# Backplane.net
KiCad netlist of a schematic drawn in EAGLE
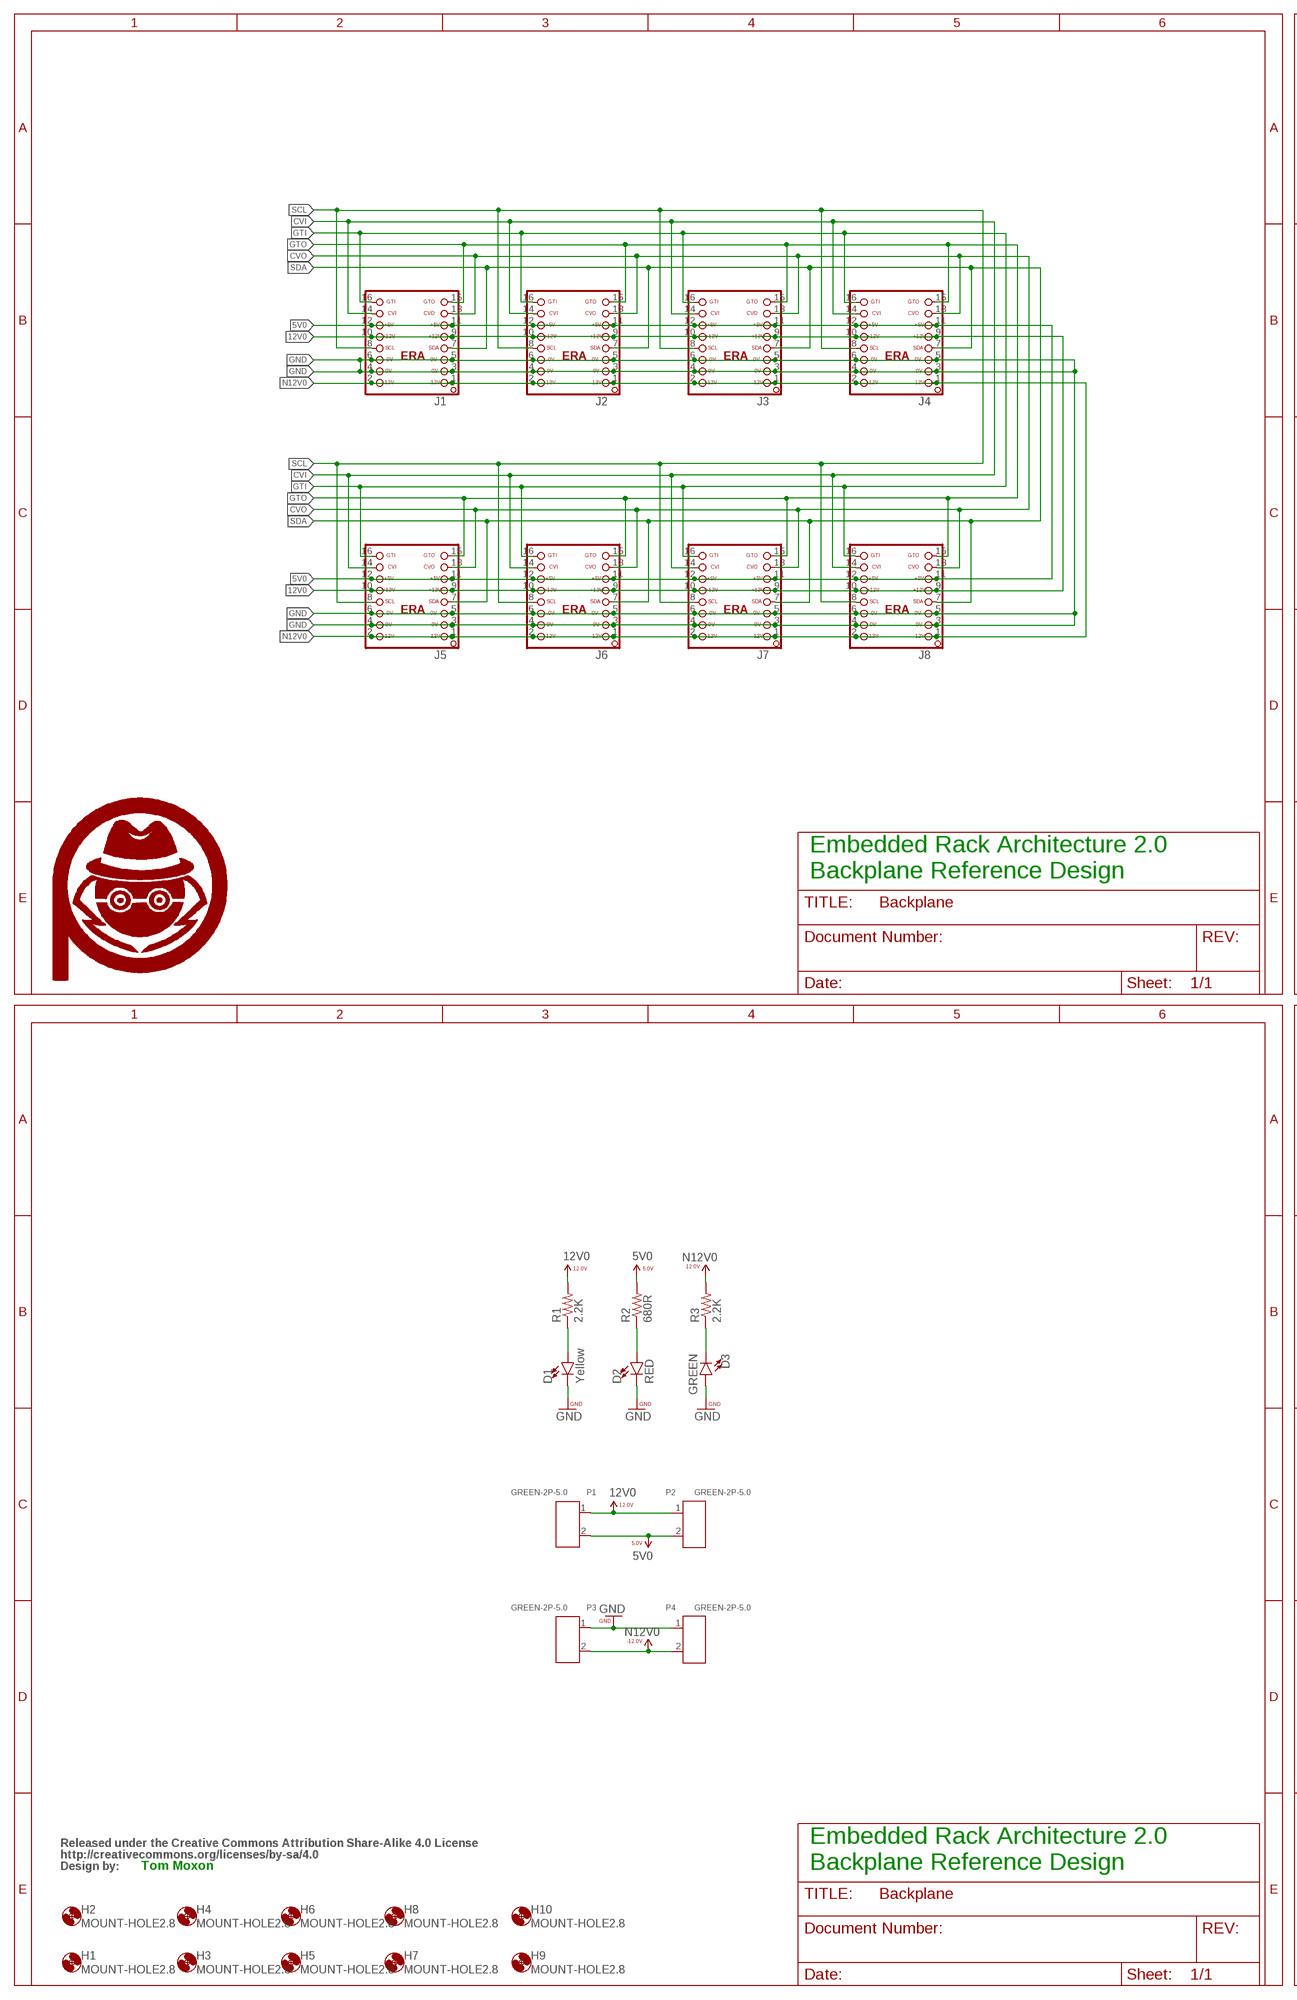
[diagram p0: schematic, sheet 1, part 1 of 2]
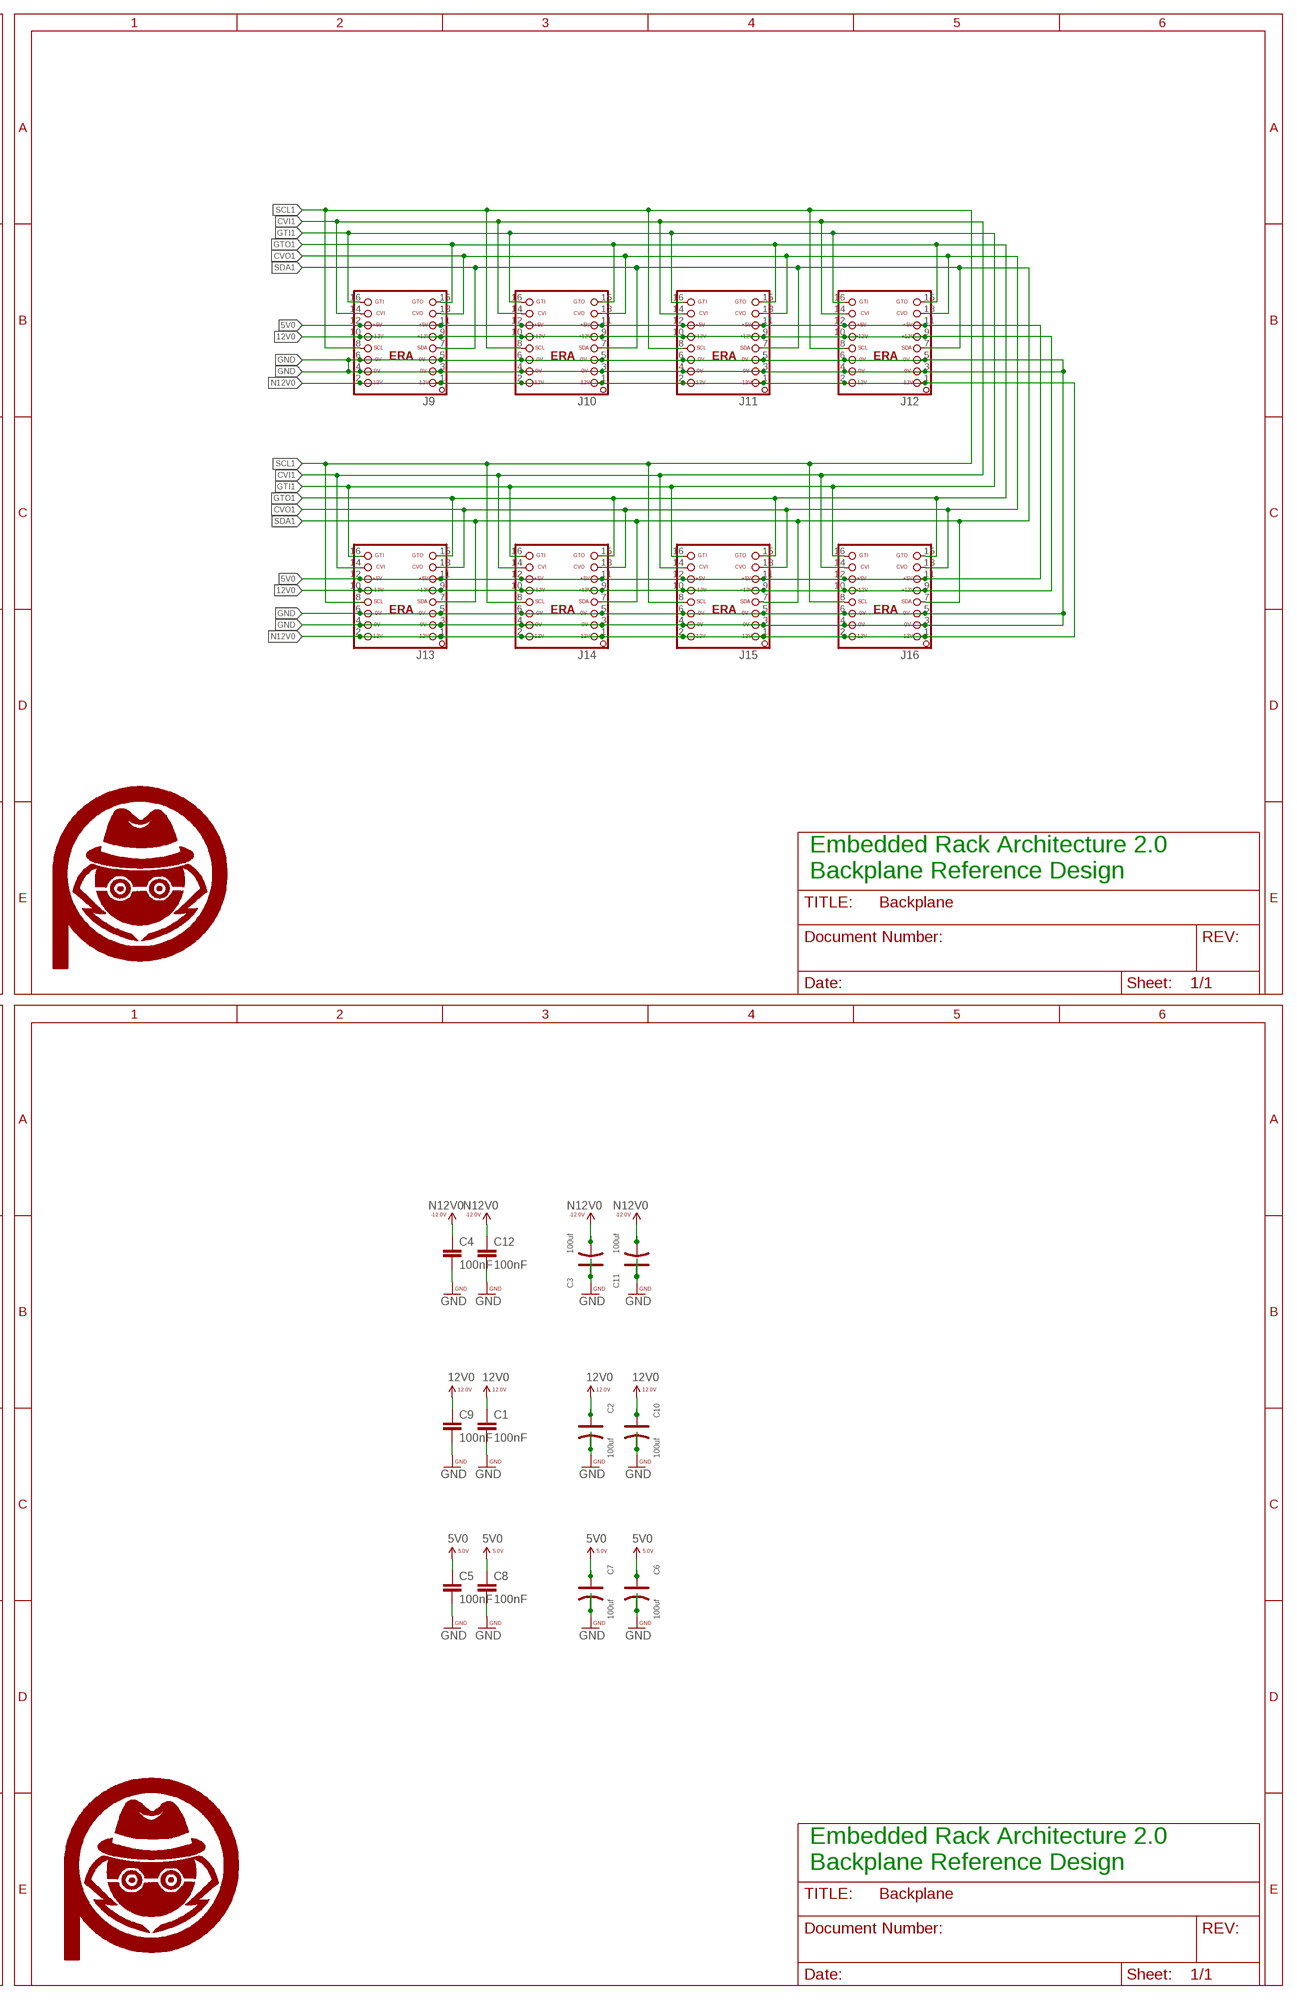
[diagram p1: schematic, sheet 1, part 2 of 2]

(export (version "E")
  (design (tool "Eeschema 10.0.6"))
  (components
    (comp (ref "C1")
      (value "100nF")
      (footprint "eagle-import:0603-CAP")
      (libsource (lib "eagle-import") (part "CAP0603-CAP"))
    )
    (comp (ref "C2")
      (value "100uf")
      (footprint "eagle-import:PC-D5.3MM")
      (fields (field (name "MPN") "KS 100uF/16V"))
      (libsource (lib "eagle-import") (part "DIP-ALUMINUM-100UF-16V(D5-H7MM)"))
    )
    (comp (ref "C3")
      (value "100uf")
      (footprint "eagle-import:PC-D5.3MM")
      (fields (field (name "MPN") "KS 100uF/16V"))
      (libsource (lib "eagle-import") (part "DIP-ALUMINUM-100UF-16V(D5-H7MM)"))
    )
    (comp (ref "C4")
      (value "100nF")
      (footprint "eagle-import:0603-CAP")
      (libsource (lib "eagle-import") (part "CAP0603-CAP"))
    )
    (comp (ref "C5")
      (value "100nF")
      (footprint "eagle-import:0603-CAP")
      (libsource (lib "eagle-import") (part "CAP0603-CAP"))
    )
    (comp (ref "C6")
      (value "100uf")
      (footprint "eagle-import:PC-D5.3MM")
      (fields (field (name "MPN") "KS 100uF/16V"))
      (libsource (lib "eagle-import") (part "DIP-ALUMINUM-100UF-16V(D5-H7MM)"))
    )
    (comp (ref "C7")
      (value "100uf")
      (footprint "eagle-import:PC-D5.3MM")
      (fields (field (name "MPN") "KS 100uF/16V"))
      (libsource (lib "eagle-import") (part "DIP-ALUMINUM-100UF-16V(D5-H7MM)"))
    )
    (comp (ref "C8")
      (value "100nF")
      (footprint "eagle-import:0603-CAP")
      (libsource (lib "eagle-import") (part "CAP0603-CAP"))
    )
    (comp (ref "C9")
      (value "100nF")
      (footprint "eagle-import:0603-CAP")
      (libsource (lib "eagle-import") (part "CAP0603-CAP"))
    )
    (comp (ref "C10")
      (value "100uf")
      (footprint "eagle-import:PC-D5.3MM")
      (fields (field (name "MPN") "KS 100uF/16V"))
      (libsource (lib "eagle-import") (part "DIP-ALUMINUM-100UF-16V(D5-H7MM)"))
    )
    (comp (ref "C11")
      (value "100uf")
      (footprint "eagle-import:PC-D5.3MM")
      (fields (field (name "MPN") "KS 100uF/16V"))
      (libsource (lib "eagle-import") (part "DIP-ALUMINUM-100UF-16V(D5-H7MM)"))
    )
    (comp (ref "C12")
      (value "100nF")
      (footprint "eagle-import:0603-CAP")
      (libsource (lib "eagle-import") (part "CAP0603-CAP"))
    )
    (comp (ref "D1")
      (value "Yellow")
      (footprint "eagle-import:LED-0603")
      (libsource (lib "eagle-import") (part "LED-YELLOW0603"))
    )
    (comp (ref "D2")
      (value "RED")
      (footprint "eagle-import:LED-0603")
      (libsource (lib "eagle-import") (part "LED-RED0603"))
    )
    (comp (ref "D3")
      (value "GREEN")
      (footprint "eagle-import:LED-0603")
      (libsource (lib "eagle-import") (part "LED-GREEN0603"))
    )
    (comp (ref "H1")
      (value "MOUNT-HOLE2.8")
      (footprint "eagle-import:2,8")
      (libsource (lib "eagle-import") (part "MOUNT-HOLE2.8"))
    )
    (comp (ref "H2")
      (value "MOUNT-HOLE2.8")
      (footprint "eagle-import:2,8")
      (libsource (lib "eagle-import") (part "MOUNT-HOLE2.8"))
    )
    (comp (ref "H3")
      (value "MOUNT-HOLE2.8")
      (footprint "eagle-import:2,8")
      (libsource (lib "eagle-import") (part "MOUNT-HOLE2.8"))
    )
    (comp (ref "H4")
      (value "MOUNT-HOLE2.8")
      (footprint "eagle-import:2,8")
      (libsource (lib "eagle-import") (part "MOUNT-HOLE2.8"))
    )
    (comp (ref "H5")
      (value "MOUNT-HOLE2.8")
      (footprint "eagle-import:2,8")
      (libsource (lib "eagle-import") (part "MOUNT-HOLE2.8"))
    )
    (comp (ref "H6")
      (value "MOUNT-HOLE2.8")
      (footprint "eagle-import:2,8")
      (libsource (lib "eagle-import") (part "MOUNT-HOLE2.8"))
    )
    (comp (ref "H7")
      (value "MOUNT-HOLE2.8")
      (footprint "eagle-import:2,8")
      (libsource (lib "eagle-import") (part "MOUNT-HOLE2.8"))
    )
    (comp (ref "H8")
      (value "MOUNT-HOLE2.8")
      (footprint "eagle-import:2,8")
      (libsource (lib "eagle-import") (part "MOUNT-HOLE2.8"))
    )
    (comp (ref "H9")
      (value "MOUNT-HOLE2.8")
      (footprint "eagle-import:2,8")
      (libsource (lib "eagle-import") (part "MOUNT-HOLE2.8"))
    )
    (comp (ref "H10")
      (value "MOUNT-HOLE2.8")
      (footprint "eagle-import:2,8")
      (libsource (lib "eagle-import") (part "MOUNT-HOLE2.8"))
    )
    (comp (ref "J1")
      (value "ERA-SHROUD")
      (footprint "eagle-import:ERA")
      (libsource (lib "eagle-import") (part "ERA-SHROUD"))
    )
    (comp (ref "J2")
      (value "ERA-SHROUD")
      (footprint "eagle-import:ERA")
      (libsource (lib "eagle-import") (part "ERA-SHROUD"))
    )
    (comp (ref "J3")
      (value "ERA-SHROUD")
      (footprint "eagle-import:ERA")
      (libsource (lib "eagle-import") (part "ERA-SHROUD"))
    )
    (comp (ref "J4")
      (value "ERA-SHROUD")
      (footprint "eagle-import:ERA")
      (libsource (lib "eagle-import") (part "ERA-SHROUD"))
    )
    (comp (ref "J5")
      (value "ERA-SHROUD")
      (footprint "eagle-import:ERA")
      (libsource (lib "eagle-import") (part "ERA-SHROUD"))
    )
    (comp (ref "J6")
      (value "ERA-SHROUD")
      (footprint "eagle-import:ERA")
      (libsource (lib "eagle-import") (part "ERA-SHROUD"))
    )
    (comp (ref "J7")
      (value "ERA-SHROUD")
      (footprint "eagle-import:ERA")
      (libsource (lib "eagle-import") (part "ERA-SHROUD"))
    )
    (comp (ref "J8")
      (value "ERA-SHROUD")
      (footprint "eagle-import:ERA")
      (libsource (lib "eagle-import") (part "ERA-SHROUD"))
    )
    (comp (ref "J9")
      (value "ERA-SHROUD")
      (footprint "eagle-import:ERA")
      (libsource (lib "eagle-import") (part "ERA-SHROUD"))
    )
    (comp (ref "J10")
      (value "ERA-SHROUD")
      (footprint "eagle-import:ERA")
      (libsource (lib "eagle-import") (part "ERA-SHROUD"))
    )
    (comp (ref "J11")
      (value "ERA-SHROUD")
      (footprint "eagle-import:ERA")
      (libsource (lib "eagle-import") (part "ERA-SHROUD"))
    )
    (comp (ref "J12")
      (value "ERA-SHROUD")
      (footprint "eagle-import:ERA")
      (libsource (lib "eagle-import") (part "ERA-SHROUD"))
    )
    (comp (ref "J13")
      (value "ERA-SHROUD")
      (footprint "eagle-import:ERA")
      (libsource (lib "eagle-import") (part "ERA-SHROUD"))
    )
    (comp (ref "J14")
      (value "ERA-SHROUD")
      (footprint "eagle-import:ERA")
      (libsource (lib "eagle-import") (part "ERA-SHROUD"))
    )
    (comp (ref "J15")
      (value "ERA-SHROUD")
      (footprint "eagle-import:ERA")
      (libsource (lib "eagle-import") (part "ERA-SHROUD"))
    )
    (comp (ref "J16")
      (value "ERA-SHROUD")
      (footprint "eagle-import:ERA")
      (libsource (lib "eagle-import") (part "ERA-SHROUD"))
    )
    (comp (ref "P1")
      (value "GREEN-2P-5.0")
      (footprint "eagle-import:H2-5.0-10.5X8.0MM")
      (libsource (lib "eagle-import") (part "SCREW-TERMINAL-GREEN(2P-5.0)"))
    )
    (comp (ref "P2")
      (value "GREEN-2P-5.0")
      (footprint "eagle-import:H2-5.0-10.5X8.0MM")
      (libsource (lib "eagle-import") (part "SCREW-TERMINAL-GREEN(2P-5.0)"))
    )
    (comp (ref "P3")
      (value "GREEN-2P-5.0")
      (footprint "eagle-import:H2-5.0-10.5X8.0MM")
      (libsource (lib "eagle-import") (part "SCREW-TERMINAL-GREEN(2P-5.0)"))
    )
    (comp (ref "P4")
      (value "GREEN-2P-5.0")
      (footprint "eagle-import:H2-5.0-10.5X8.0MM")
      (libsource (lib "eagle-import") (part "SCREW-TERMINAL-GREEN(2P-5.0)"))
    )
    (comp (ref "R1")
      (value "2.2K")
      (footprint "eagle-import:0603-RES")
      (libsource (lib "eagle-import") (part "RESISTOR0603"))
    )
    (comp (ref "R2")
      (value "680R")
      (footprint "eagle-import:0603-RES")
      (libsource (lib "eagle-import") (part "RESISTOR0603"))
    )
    (comp (ref "R3")
      (value "2.2K")
      (footprint "eagle-import:0603-RES")
      (libsource (lib "eagle-import") (part "RESISTOR0603"))
    )
    (comp (ref "U$19")
      (value "PA_LOGO_SYMMED")
      (footprint "eagle-import:PA_LOGO_AGENT_MED_SYM")
      (libsource (lib "eagle-import") (part "PA_LOGO_SYMMED"))
    )
    (comp (ref "U$37")
      (value "PA_LOGO_SYMMED")
      (footprint "eagle-import:PA_LOGO_AGENT_MED_SYM")
      (libsource (lib "eagle-import") (part "PA_LOGO_SYMMED"))
    )
    (comp (ref "U$38")
      (value "PA_LOGO_SYMLARGE")
      (footprint "eagle-import:PA_LOGO_AGENT_LRG_SYM")
      (libsource (lib "eagle-import") (part "PA_LOGO_SYMLARGE"))
    )
    (comp (ref "U$48")
      (value "BY_CC_SA_TEXTTEXT")
      (footprint "eagle-import:BY_CC_SA_TEXT")
      (libsource (lib "eagle-import") (part "BY_CC_SA_TEXTTEXT"))
    )
  )
  (nets
    (net (code "1") (name "5V0") (class "Default")
      (node (ref "C5") (pin "1") (pinfunction "1_1") (pintype "passive"))
      (node (ref "C6") (pin "+") (pinfunction "+_+") (pintype "passive"))
      (node (ref "C7") (pin "+") (pinfunction "+_+") (pintype "passive"))
      (node (ref "C8") (pin "1") (pinfunction "1_1") (pintype "passive"))
      (node (ref "J1") (pin "11") (pinfunction "11_11") (pintype "passive"))
      (node (ref "J1") (pin "12") (pinfunction "12_12") (pintype "passive"))
      (node (ref "J10") (pin "11") (pinfunction "11_11") (pintype "passive"))
      (node (ref "J10") (pin "12") (pinfunction "12_12") (pintype "passive"))
      (node (ref "J11") (pin "11") (pinfunction "11_11") (pintype "passive"))
      (node (ref "J11") (pin "12") (pinfunction "12_12") (pintype "passive"))
      (node (ref "J12") (pin "11") (pinfunction "11_11") (pintype "passive"))
      (node (ref "J12") (pin "12") (pinfunction "12_12") (pintype "passive"))
      (node (ref "J13") (pin "11") (pinfunction "11_11") (pintype "passive"))
      (node (ref "J13") (pin "12") (pinfunction "12_12") (pintype "passive"))
      (node (ref "J14") (pin "11") (pinfunction "11_11") (pintype "passive"))
      (node (ref "J14") (pin "12") (pinfunction "12_12") (pintype "passive"))
      (node (ref "J15") (pin "11") (pinfunction "11_11") (pintype "passive"))
      (node (ref "J15") (pin "12") (pinfunction "12_12") (pintype "passive"))
      (node (ref "J16") (pin "11") (pinfunction "11_11") (pintype "passive"))
      (node (ref "J16") (pin "12") (pinfunction "12_12") (pintype "passive"))
      (node (ref "J2") (pin "11") (pinfunction "11_11") (pintype "passive"))
      (node (ref "J2") (pin "12") (pinfunction "12_12") (pintype "passive"))
      (node (ref "J3") (pin "11") (pinfunction "11_11") (pintype "passive"))
      (node (ref "J3") (pin "12") (pinfunction "12_12") (pintype "passive"))
      (node (ref "J4") (pin "11") (pinfunction "11_11") (pintype "passive"))
      (node (ref "J4") (pin "12") (pinfunction "12_12") (pintype "passive"))
      (node (ref "J5") (pin "11") (pinfunction "11_11") (pintype "passive"))
      (node (ref "J5") (pin "12") (pinfunction "12_12") (pintype "passive"))
      (node (ref "J6") (pin "11") (pinfunction "11_11") (pintype "passive"))
      (node (ref "J6") (pin "12") (pinfunction "12_12") (pintype "passive"))
      (node (ref "J7") (pin "11") (pinfunction "11_11") (pintype "passive"))
      (node (ref "J7") (pin "12") (pinfunction "12_12") (pintype "passive"))
      (node (ref "J8") (pin "11") (pinfunction "11_11") (pintype "passive"))
      (node (ref "J8") (pin "12") (pinfunction "12_12") (pintype "passive"))
      (node (ref "J9") (pin "11") (pinfunction "11_11") (pintype "passive"))
      (node (ref "J9") (pin "12") (pinfunction "12_12") (pintype "passive"))
      (node (ref "P1") (pin "2") (pinfunction "2_2") (pintype "bidirectional"))
      (node (ref "P2") (pin "2") (pinfunction "2_2") (pintype "bidirectional"))
      (node (ref "R2") (pin "2") (pinfunction "2_2") (pintype "passive"))
    )
    (net (code "2") (name "12V0") (class "Default")
      (node (ref "C1") (pin "1") (pinfunction "1_1") (pintype "passive"))
      (node (ref "C10") (pin "+") (pinfunction "+_+") (pintype "passive"))
      (node (ref "C2") (pin "+") (pinfunction "+_+") (pintype "passive"))
      (node (ref "C9") (pin "1") (pinfunction "1_1") (pintype "passive"))
      (node (ref "J1") (pin "10") (pinfunction "10_10") (pintype "passive"))
      (node (ref "J1") (pin "9") (pinfunction "9_9") (pintype "passive"))
      (node (ref "J10") (pin "10") (pinfunction "10_10") (pintype "passive"))
      (node (ref "J10") (pin "9") (pinfunction "9_9") (pintype "passive"))
      (node (ref "J11") (pin "10") (pinfunction "10_10") (pintype "passive"))
      (node (ref "J11") (pin "9") (pinfunction "9_9") (pintype "passive"))
      (node (ref "J12") (pin "10") (pinfunction "10_10") (pintype "passive"))
      (node (ref "J12") (pin "9") (pinfunction "9_9") (pintype "passive"))
      (node (ref "J13") (pin "10") (pinfunction "10_10") (pintype "passive"))
      (node (ref "J13") (pin "9") (pinfunction "9_9") (pintype "passive"))
      (node (ref "J14") (pin "10") (pinfunction "10_10") (pintype "passive"))
      (node (ref "J14") (pin "9") (pinfunction "9_9") (pintype "passive"))
      (node (ref "J15") (pin "10") (pinfunction "10_10") (pintype "passive"))
      (node (ref "J15") (pin "9") (pinfunction "9_9") (pintype "passive"))
      (node (ref "J16") (pin "10") (pinfunction "10_10") (pintype "passive"))
      (node (ref "J16") (pin "9") (pinfunction "9_9") (pintype "passive"))
      (node (ref "J2") (pin "10") (pinfunction "10_10") (pintype "passive"))
      (node (ref "J2") (pin "9") (pinfunction "9_9") (pintype "passive"))
      (node (ref "J3") (pin "10") (pinfunction "10_10") (pintype "passive"))
      (node (ref "J3") (pin "9") (pinfunction "9_9") (pintype "passive"))
      (node (ref "J4") (pin "10") (pinfunction "10_10") (pintype "passive"))
      (node (ref "J4") (pin "9") (pinfunction "9_9") (pintype "passive"))
      (node (ref "J5") (pin "10") (pinfunction "10_10") (pintype "passive"))
      (node (ref "J5") (pin "9") (pinfunction "9_9") (pintype "passive"))
      (node (ref "J6") (pin "10") (pinfunction "10_10") (pintype "passive"))
      (node (ref "J6") (pin "9") (pinfunction "9_9") (pintype "passive"))
      (node (ref "J7") (pin "10") (pinfunction "10_10") (pintype "passive"))
      (node (ref "J7") (pin "9") (pinfunction "9_9") (pintype "passive"))
      (node (ref "J8") (pin "10") (pinfunction "10_10") (pintype "passive"))
      (node (ref "J8") (pin "9") (pinfunction "9_9") (pintype "passive"))
      (node (ref "J9") (pin "10") (pinfunction "10_10") (pintype "passive"))
      (node (ref "J9") (pin "9") (pinfunction "9_9") (pintype "passive"))
      (node (ref "P1") (pin "1") (pinfunction "1_1") (pintype "bidirectional"))
      (node (ref "P2") (pin "1") (pinfunction "1_1") (pintype "bidirectional"))
      (node (ref "R1") (pin "2") (pinfunction "2_2") (pintype "passive"))
    )
    (net (code "3") (name "CVI") (class "Default")
      (node (ref "J1") (pin "14") (pinfunction "14_14") (pintype "passive"))
      (node (ref "J2") (pin "14") (pinfunction "14_14") (pintype "passive"))
      (node (ref "J3") (pin "14") (pinfunction "14_14") (pintype "passive"))
      (node (ref "J4") (pin "14") (pinfunction "14_14") (pintype "passive"))
      (node (ref "J5") (pin "14") (pinfunction "14_14") (pintype "passive"))
      (node (ref "J6") (pin "14") (pinfunction "14_14") (pintype "passive"))
      (node (ref "J7") (pin "14") (pinfunction "14_14") (pintype "passive"))
      (node (ref "J8") (pin "14") (pinfunction "14_14") (pintype "passive"))
    )
    (net (code "4") (name "CVI1") (class "Default")
      (node (ref "J10") (pin "14") (pinfunction "14_14") (pintype "passive"))
      (node (ref "J11") (pin "14") (pinfunction "14_14") (pintype "passive"))
      (node (ref "J12") (pin "14") (pinfunction "14_14") (pintype "passive"))
      (node (ref "J13") (pin "14") (pinfunction "14_14") (pintype "passive"))
      (node (ref "J14") (pin "14") (pinfunction "14_14") (pintype "passive"))
      (node (ref "J15") (pin "14") (pinfunction "14_14") (pintype "passive"))
      (node (ref "J16") (pin "14") (pinfunction "14_14") (pintype "passive"))
      (node (ref "J9") (pin "14") (pinfunction "14_14") (pintype "passive"))
    )
    (net (code "5") (name "CVO") (class "Default")
      (node (ref "J1") (pin "13") (pinfunction "13_13") (pintype "passive"))
      (node (ref "J2") (pin "13") (pinfunction "13_13") (pintype "passive"))
      (node (ref "J3") (pin "13") (pinfunction "13_13") (pintype "passive"))
      (node (ref "J4") (pin "13") (pinfunction "13_13") (pintype "passive"))
      (node (ref "J5") (pin "13") (pinfunction "13_13") (pintype "passive"))
      (node (ref "J6") (pin "13") (pinfunction "13_13") (pintype "passive"))
      (node (ref "J7") (pin "13") (pinfunction "13_13") (pintype "passive"))
      (node (ref "J8") (pin "13") (pinfunction "13_13") (pintype "passive"))
    )
    (net (code "6") (name "CVO1") (class "Default")
      (node (ref "J10") (pin "13") (pinfunction "13_13") (pintype "passive"))
      (node (ref "J11") (pin "13") (pinfunction "13_13") (pintype "passive"))
      (node (ref "J12") (pin "13") (pinfunction "13_13") (pintype "passive"))
      (node (ref "J13") (pin "13") (pinfunction "13_13") (pintype "passive"))
      (node (ref "J14") (pin "13") (pinfunction "13_13") (pintype "passive"))
      (node (ref "J15") (pin "13") (pinfunction "13_13") (pintype "passive"))
      (node (ref "J16") (pin "13") (pinfunction "13_13") (pintype "passive"))
      (node (ref "J9") (pin "13") (pinfunction "13_13") (pintype "passive"))
    )
    (net (code "7") (name "GND") (class "Default")
      (node (ref "C1") (pin "2") (pinfunction "2_2") (pintype "passive"))
      (node (ref "C10") (pin "-") (pinfunction "-_-") (pintype "passive"))
      (node (ref "C11") (pin "+") (pinfunction "+_+") (pintype "passive"))
      (node (ref "C12") (pin "2") (pinfunction "2_2") (pintype "passive"))
      (node (ref "C2") (pin "-") (pinfunction "-_-") (pintype "passive"))
      (node (ref "C3") (pin "+") (pinfunction "+_+") (pintype "passive"))
      (node (ref "C4") (pin "2") (pinfunction "2_2") (pintype "passive"))
      (node (ref "C5") (pin "2") (pinfunction "2_2") (pintype "passive"))
      (node (ref "C6") (pin "-") (pinfunction "-_-") (pintype "passive"))
      (node (ref "C7") (pin "-") (pinfunction "-_-") (pintype "passive"))
      (node (ref "C8") (pin "2") (pinfunction "2_2") (pintype "passive"))
      (node (ref "C9") (pin "2") (pinfunction "2_2") (pintype "passive"))
      (node (ref "D1") (pin "C") (pinfunction "C_C") (pintype "passive"))
      (node (ref "D2") (pin "C") (pinfunction "C_C") (pintype "passive"))
      (node (ref "D3") (pin "A") (pinfunction "A_A") (pintype "passive"))
      (node (ref "J1") (pin "3") (pinfunction "3_3") (pintype "passive"))
      (node (ref "J1") (pin "4") (pinfunction "4_4") (pintype "passive"))
      (node (ref "J1") (pin "5") (pinfunction "5_5") (pintype "passive"))
      (node (ref "J1") (pin "6") (pinfunction "6_6") (pintype "passive"))
      (node (ref "J10") (pin "3") (pinfunction "3_3") (pintype "passive"))
      (node (ref "J10") (pin "4") (pinfunction "4_4") (pintype "passive"))
      (node (ref "J10") (pin "5") (pinfunction "5_5") (pintype "passive"))
      (node (ref "J10") (pin "6") (pinfunction "6_6") (pintype "passive"))
      (node (ref "J11") (pin "3") (pinfunction "3_3") (pintype "passive"))
      (node (ref "J11") (pin "4") (pinfunction "4_4") (pintype "passive"))
      (node (ref "J11") (pin "5") (pinfunction "5_5") (pintype "passive"))
      (node (ref "J11") (pin "6") (pinfunction "6_6") (pintype "passive"))
      (node (ref "J12") (pin "3") (pinfunction "3_3") (pintype "passive"))
      (node (ref "J12") (pin "4") (pinfunction "4_4") (pintype "passive"))
      (node (ref "J12") (pin "5") (pinfunction "5_5") (pintype "passive"))
      (node (ref "J12") (pin "6") (pinfunction "6_6") (pintype "passive"))
      (node (ref "J13") (pin "3") (pinfunction "3_3") (pintype "passive"))
      (node (ref "J13") (pin "4") (pinfunction "4_4") (pintype "passive"))
      (node (ref "J13") (pin "5") (pinfunction "5_5") (pintype "passive"))
      (node (ref "J13") (pin "6") (pinfunction "6_6") (pintype "passive"))
      (node (ref "J14") (pin "3") (pinfunction "3_3") (pintype "passive"))
      (node (ref "J14") (pin "4") (pinfunction "4_4") (pintype "passive"))
      (node (ref "J14") (pin "5") (pinfunction "5_5") (pintype "passive"))
      (node (ref "J14") (pin "6") (pinfunction "6_6") (pintype "passive"))
      (node (ref "J15") (pin "3") (pinfunction "3_3") (pintype "passive"))
      (node (ref "J15") (pin "4") (pinfunction "4_4") (pintype "passive"))
      (node (ref "J15") (pin "5") (pinfunction "5_5") (pintype "passive"))
      (node (ref "J15") (pin "6") (pinfunction "6_6") (pintype "passive"))
      (node (ref "J16") (pin "3") (pinfunction "3_3") (pintype "passive"))
      (node (ref "J16") (pin "4") (pinfunction "4_4") (pintype "passive"))
      (node (ref "J16") (pin "5") (pinfunction "5_5") (pintype "passive"))
      (node (ref "J16") (pin "6") (pinfunction "6_6") (pintype "passive"))
      (node (ref "J2") (pin "3") (pinfunction "3_3") (pintype "passive"))
      (node (ref "J2") (pin "4") (pinfunction "4_4") (pintype "passive"))
      (node (ref "J2") (pin "5") (pinfunction "5_5") (pintype "passive"))
      (node (ref "J2") (pin "6") (pinfunction "6_6") (pintype "passive"))
      (node (ref "J3") (pin "3") (pinfunction "3_3") (pintype "passive"))
      (node (ref "J3") (pin "4") (pinfunction "4_4") (pintype "passive"))
      (node (ref "J3") (pin "5") (pinfunction "5_5") (pintype "passive"))
      (node (ref "J3") (pin "6") (pinfunction "6_6") (pintype "passive"))
      (node (ref "J4") (pin "3") (pinfunction "3_3") (pintype "passive"))
      (node (ref "J4") (pin "4") (pinfunction "4_4") (pintype "passive"))
      (node (ref "J4") (pin "5") (pinfunction "5_5") (pintype "passive"))
      (node (ref "J4") (pin "6") (pinfunction "6_6") (pintype "passive"))
      (node (ref "J5") (pin "3") (pinfunction "3_3") (pintype "passive"))
      (node (ref "J5") (pin "4") (pinfunction "4_4") (pintype "passive"))
      (node (ref "J5") (pin "5") (pinfunction "5_5") (pintype "passive"))
      (node (ref "J5") (pin "6") (pinfunction "6_6") (pintype "passive"))
      (node (ref "J6") (pin "3") (pinfunction "3_3") (pintype "passive"))
      (node (ref "J6") (pin "4") (pinfunction "4_4") (pintype "passive"))
      (node (ref "J6") (pin "5") (pinfunction "5_5") (pintype "passive"))
      (node (ref "J6") (pin "6") (pinfunction "6_6") (pintype "passive"))
      (node (ref "J7") (pin "3") (pinfunction "3_3") (pintype "passive"))
      (node (ref "J7") (pin "4") (pinfunction "4_4") (pintype "passive"))
      (node (ref "J7") (pin "5") (pinfunction "5_5") (pintype "passive"))
      (node (ref "J7") (pin "6") (pinfunction "6_6") (pintype "passive"))
      (node (ref "J8") (pin "3") (pinfunction "3_3") (pintype "passive"))
      (node (ref "J8") (pin "4") (pinfunction "4_4") (pintype "passive"))
      (node (ref "J8") (pin "5") (pinfunction "5_5") (pintype "passive"))
      (node (ref "J8") (pin "6") (pinfunction "6_6") (pintype "passive"))
      (node (ref "J9") (pin "3") (pinfunction "3_3") (pintype "passive"))
      (node (ref "J9") (pin "4") (pinfunction "4_4") (pintype "passive"))
      (node (ref "J9") (pin "5") (pinfunction "5_5") (pintype "passive"))
      (node (ref "J9") (pin "6") (pinfunction "6_6") (pintype "passive"))
      (node (ref "P3") (pin "1") (pinfunction "1_1") (pintype "bidirectional"))
      (node (ref "P4") (pin "1") (pinfunction "1_1") (pintype "bidirectional"))
    )
    (net (code "8") (name "GTI") (class "Default")
      (node (ref "J1") (pin "16") (pinfunction "16_16") (pintype "passive"))
      (node (ref "J2") (pin "16") (pinfunction "16_16") (pintype "passive"))
      (node (ref "J3") (pin "16") (pinfunction "16_16") (pintype "passive"))
      (node (ref "J4") (pin "16") (pinfunction "16_16") (pintype "passive"))
      (node (ref "J5") (pin "16") (pinfunction "16_16") (pintype "passive"))
      (node (ref "J6") (pin "16") (pinfunction "16_16") (pintype "passive"))
      (node (ref "J7") (pin "16") (pinfunction "16_16") (pintype "passive"))
      (node (ref "J8") (pin "16") (pinfunction "16_16") (pintype "passive"))
    )
    (net (code "9") (name "GTI1") (class "Default")
      (node (ref "J10") (pin "16") (pinfunction "16_16") (pintype "passive"))
      (node (ref "J11") (pin "16") (pinfunction "16_16") (pintype "passive"))
      (node (ref "J12") (pin "16") (pinfunction "16_16") (pintype "passive"))
      (node (ref "J13") (pin "16") (pinfunction "16_16") (pintype "passive"))
      (node (ref "J14") (pin "16") (pinfunction "16_16") (pintype "passive"))
      (node (ref "J15") (pin "16") (pinfunction "16_16") (pintype "passive"))
      (node (ref "J16") (pin "16") (pinfunction "16_16") (pintype "passive"))
      (node (ref "J9") (pin "16") (pinfunction "16_16") (pintype "passive"))
    )
    (net (code "10") (name "GTO") (class "Default")
      (node (ref "J1") (pin "15") (pinfunction "15_15") (pintype "passive"))
      (node (ref "J2") (pin "15") (pinfunction "15_15") (pintype "passive"))
      (node (ref "J3") (pin "15") (pinfunction "15_15") (pintype "passive"))
      (node (ref "J4") (pin "15") (pinfunction "15_15") (pintype "passive"))
      (node (ref "J5") (pin "15") (pinfunction "15_15") (pintype "passive"))
      (node (ref "J6") (pin "15") (pinfunction "15_15") (pintype "passive"))
      (node (ref "J7") (pin "15") (pinfunction "15_15") (pintype "passive"))
      (node (ref "J8") (pin "15") (pinfunction "15_15") (pintype "passive"))
    )
    (net (code "11") (name "GTO1") (class "Default")
      (node (ref "J10") (pin "15") (pinfunction "15_15") (pintype "passive"))
      (node (ref "J11") (pin "15") (pinfunction "15_15") (pintype "passive"))
      (node (ref "J12") (pin "15") (pinfunction "15_15") (pintype "passive"))
      (node (ref "J13") (pin "15") (pinfunction "15_15") (pintype "passive"))
      (node (ref "J14") (pin "15") (pinfunction "15_15") (pintype "passive"))
      (node (ref "J15") (pin "15") (pinfunction "15_15") (pintype "passive"))
      (node (ref "J16") (pin "15") (pinfunction "15_15") (pintype "passive"))
      (node (ref "J9") (pin "15") (pinfunction "15_15") (pintype "passive"))
    )
    (net (code "12") (name "N12V0") (class "Default")
      (node (ref "C11") (pin "-") (pinfunction "-_-") (pintype "passive"))
      (node (ref "C12") (pin "1") (pinfunction "1_1") (pintype "passive"))
      (node (ref "C3") (pin "-") (pinfunction "-_-") (pintype "passive"))
      (node (ref "C4") (pin "1") (pinfunction "1_1") (pintype "passive"))
      (node (ref "J1") (pin "1") (pinfunction "1_1") (pintype "passive"))
      (node (ref "J1") (pin "2") (pinfunction "2_2") (pintype "passive"))
      (node (ref "J10") (pin "1") (pinfunction "1_1") (pintype "passive"))
      (node (ref "J10") (pin "2") (pinfunction "2_2") (pintype "passive"))
      (node (ref "J11") (pin "1") (pinfunction "1_1") (pintype "passive"))
      (node (ref "J11") (pin "2") (pinfunction "2_2") (pintype "passive"))
      (node (ref "J12") (pin "1") (pinfunction "1_1") (pintype "passive"))
      (node (ref "J12") (pin "2") (pinfunction "2_2") (pintype "passive"))
      (node (ref "J13") (pin "1") (pinfunction "1_1") (pintype "passive"))
      (node (ref "J13") (pin "2") (pinfunction "2_2") (pintype "passive"))
      (node (ref "J14") (pin "1") (pinfunction "1_1") (pintype "passive"))
      (node (ref "J14") (pin "2") (pinfunction "2_2") (pintype "passive"))
      (node (ref "J15") (pin "1") (pinfunction "1_1") (pintype "passive"))
      (node (ref "J15") (pin "2") (pinfunction "2_2") (pintype "passive"))
      (node (ref "J16") (pin "1") (pinfunction "1_1") (pintype "passive"))
      (node (ref "J16") (pin "2") (pinfunction "2_2") (pintype "passive"))
      (node (ref "J2") (pin "1") (pinfunction "1_1") (pintype "passive"))
      (node (ref "J2") (pin "2") (pinfunction "2_2") (pintype "passive"))
      (node (ref "J3") (pin "1") (pinfunction "1_1") (pintype "passive"))
      (node (ref "J3") (pin "2") (pinfunction "2_2") (pintype "passive"))
      (node (ref "J4") (pin "1") (pinfunction "1_1") (pintype "passive"))
      (node (ref "J4") (pin "2") (pinfunction "2_2") (pintype "passive"))
      (node (ref "J5") (pin "1") (pinfunction "1_1") (pintype "passive"))
      (node (ref "J5") (pin "2") (pinfunction "2_2") (pintype "passive"))
      (node (ref "J6") (pin "1") (pinfunction "1_1") (pintype "passive"))
      (node (ref "J6") (pin "2") (pinfunction "2_2") (pintype "passive"))
      (node (ref "J7") (pin "1") (pinfunction "1_1") (pintype "passive"))
      (node (ref "J7") (pin "2") (pinfunction "2_2") (pintype "passive"))
      (node (ref "J8") (pin "1") (pinfunction "1_1") (pintype "passive"))
      (node (ref "J8") (pin "2") (pinfunction "2_2") (pintype "passive"))
      (node (ref "J9") (pin "1") (pinfunction "1_1") (pintype "passive"))
      (node (ref "J9") (pin "2") (pinfunction "2_2") (pintype "passive"))
      (node (ref "P3") (pin "2") (pinfunction "2_2") (pintype "bidirectional"))
      (node (ref "P4") (pin "2") (pinfunction "2_2") (pintype "bidirectional"))
      (node (ref "R3") (pin "2") (pinfunction "2_2") (pintype "passive"))
    )
    (net (code "13") (name "Net-(D1-PadA)") (class "Default")
      (node (ref "D1") (pin "A") (pinfunction "A_A") (pintype "passive"))
      (node (ref "R1") (pin "1") (pinfunction "1_1") (pintype "passive"))
    )
    (net (code "14") (name "Net-(D2-PadA)") (class "Default")
      (node (ref "D2") (pin "A") (pinfunction "A_A") (pintype "passive"))
      (node (ref "R2") (pin "1") (pinfunction "1_1") (pintype "passive"))
    )
    (net (code "15") (name "Net-(D3-PadC)") (class "Default")
      (node (ref "D3") (pin "C") (pinfunction "C_C") (pintype "passive"))
      (node (ref "R3") (pin "1") (pinfunction "1_1") (pintype "passive"))
    )
    (net (code "16") (name "SCL") (class "Default")
      (node (ref "J1") (pin "8") (pinfunction "8_8") (pintype "passive"))
      (node (ref "J2") (pin "8") (pinfunction "8_8") (pintype "passive"))
      (node (ref "J3") (pin "8") (pinfunction "8_8") (pintype "passive"))
      (node (ref "J4") (pin "8") (pinfunction "8_8") (pintype "passive"))
      (node (ref "J5") (pin "8") (pinfunction "8_8") (pintype "passive"))
      (node (ref "J6") (pin "8") (pinfunction "8_8") (pintype "passive"))
      (node (ref "J7") (pin "8") (pinfunction "8_8") (pintype "passive"))
      (node (ref "J8") (pin "8") (pinfunction "8_8") (pintype "passive"))
    )
    (net (code "17") (name "SCL1") (class "Default")
      (node (ref "J10") (pin "8") (pinfunction "8_8") (pintype "passive"))
      (node (ref "J11") (pin "8") (pinfunction "8_8") (pintype "passive"))
      (node (ref "J12") (pin "8") (pinfunction "8_8") (pintype "passive"))
      (node (ref "J13") (pin "8") (pinfunction "8_8") (pintype "passive"))
      (node (ref "J14") (pin "8") (pinfunction "8_8") (pintype "passive"))
      (node (ref "J15") (pin "8") (pinfunction "8_8") (pintype "passive"))
      (node (ref "J16") (pin "8") (pinfunction "8_8") (pintype "passive"))
      (node (ref "J9") (pin "8") (pinfunction "8_8") (pintype "passive"))
    )
    (net (code "18") (name "SDA") (class "Default")
      (node (ref "J1") (pin "7") (pinfunction "7_7") (pintype "passive"))
      (node (ref "J2") (pin "7") (pinfunction "7_7") (pintype "passive"))
      (node (ref "J3") (pin "7") (pinfunction "7_7") (pintype "passive"))
      (node (ref "J4") (pin "7") (pinfunction "7_7") (pintype "passive"))
      (node (ref "J5") (pin "7") (pinfunction "7_7") (pintype "passive"))
      (node (ref "J6") (pin "7") (pinfunction "7_7") (pintype "passive"))
      (node (ref "J7") (pin "7") (pinfunction "7_7") (pintype "passive"))
      (node (ref "J8") (pin "7") (pinfunction "7_7") (pintype "passive"))
    )
    (net (code "19") (name "SDA1") (class "Default")
      (node (ref "J10") (pin "7") (pinfunction "7_7") (pintype "passive"))
      (node (ref "J11") (pin "7") (pinfunction "7_7") (pintype "passive"))
      (node (ref "J12") (pin "7") (pinfunction "7_7") (pintype "passive"))
      (node (ref "J13") (pin "7") (pinfunction "7_7") (pintype "passive"))
      (node (ref "J14") (pin "7") (pinfunction "7_7") (pintype "passive"))
      (node (ref "J15") (pin "7") (pinfunction "7_7") (pintype "passive"))
      (node (ref "J16") (pin "7") (pinfunction "7_7") (pintype "passive"))
      (node (ref "J9") (pin "7") (pinfunction "7_7") (pintype "passive"))
    )
  )
)
